# LVR_3V3_PS.net
KiCad netlist of a schematic drawn in Altium Designer
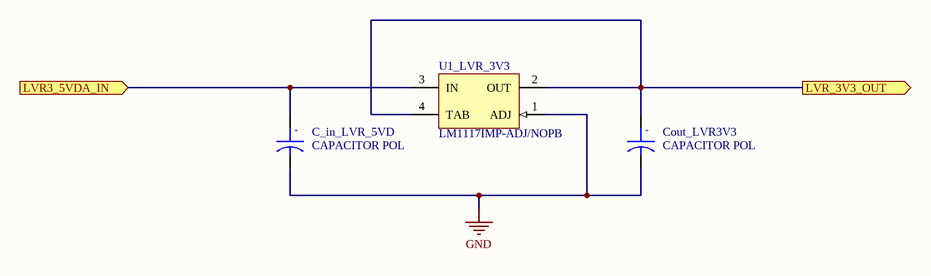
[diagram p0: LVR_3V3_PS.SchDoc]

(export (version "E")
  (design (tool "Eeschema 10.0.6"))
  (components
    (comp (ref "Cout_LVR3V3") (value "CAPACITOR POL") (libsource (lib "esd_library") (part "CAPACITOR POL")))
    (comp (ref "C_in_LVR_5VD") (value "CAPACITOR POL") (libsource (lib "esd_library") (part "CAPACITOR POL")))
    (comp (ref "U1_LVR_3V3")
      (value "LM1117IMP-ADJ/NOPB")
      (footprint "MP04A_L")
      (description "800mA Low-Dropout Linear Regulator, 4-pin SOT-223, Pb-Free")
      (fields
        (field (name "MANUFACTURER") "National Semiconductor")
        (field (name "MPN") "LM1117MP-3.3/NOPB")
        (field (name "PUBLISHER") "Altium Limited")
      )
      (libsource (lib "esd_library") (part "LM1117IMP-ADJ/NOPB"))
    )
  )
  (nets
    (net (code "1") (name "/LVR3_5VDA_IN") (class "Default")
      (node (ref "C_in_LVR_5VD") (pin "1") (pinfunction "1_1") (pintype "passive"))
      (node (ref "U1_LVR_3V3") (pin "3") (pinfunction "IN_3") (pintype "power_in"))
    )
    (net (code "2") (name "/LVR_3V3_OUT") (class "Default")
      (node (ref "Cout_LVR3V3") (pin "1") (pinfunction "1_1") (pintype "passive"))
      (node (ref "U1_LVR_3V3") (pin "2") (pinfunction "OUT_2") (pintype "power_in"))
      (node (ref "U1_LVR_3V3") (pin "4") (pinfunction "TAB_4") (pintype "power_in"))
    )
    (net (code "3") (name "GND") (class "Default")
      (node (ref "C_in_LVR_5VD") (pin "2") (pinfunction "2_2") (pintype "passive"))
      (node (ref "Cout_LVR3V3") (pin "2") (pinfunction "2_2") (pintype "passive"))
      (node (ref "U1_LVR_3V3") (pin "1") (pinfunction "ADJ_1") (pintype "input"))
    )
  )
)
